# SCH_KPHONE.net
KiCad netlist of a schematic drawn in Altium Designer
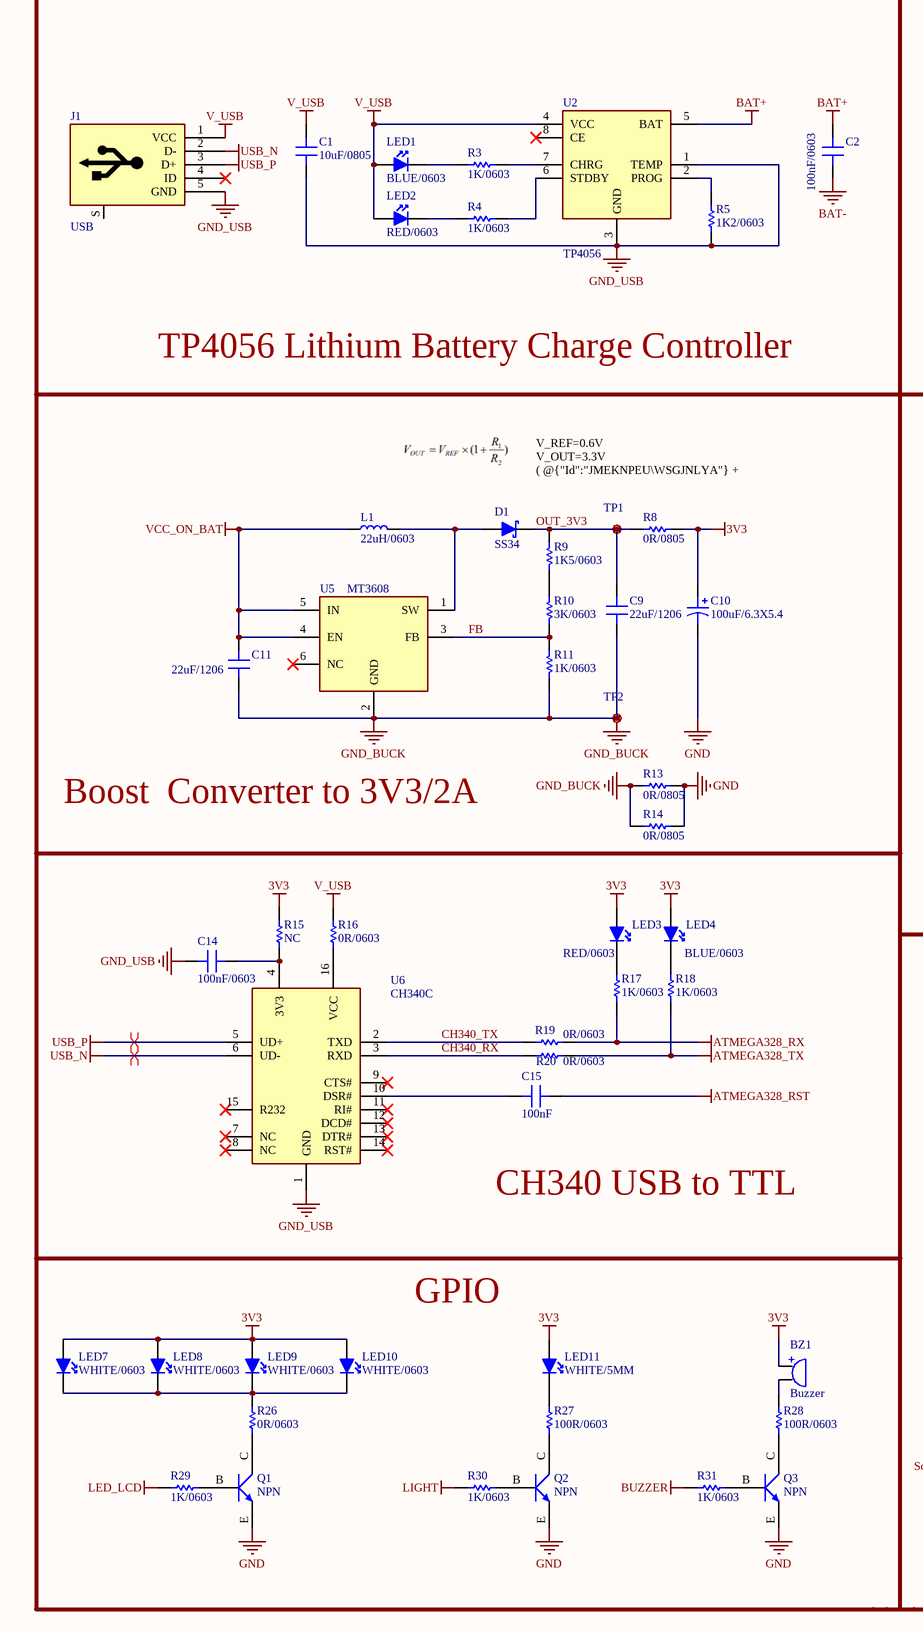
[diagram p0: SCH_KPHONE.SchDoc, left]
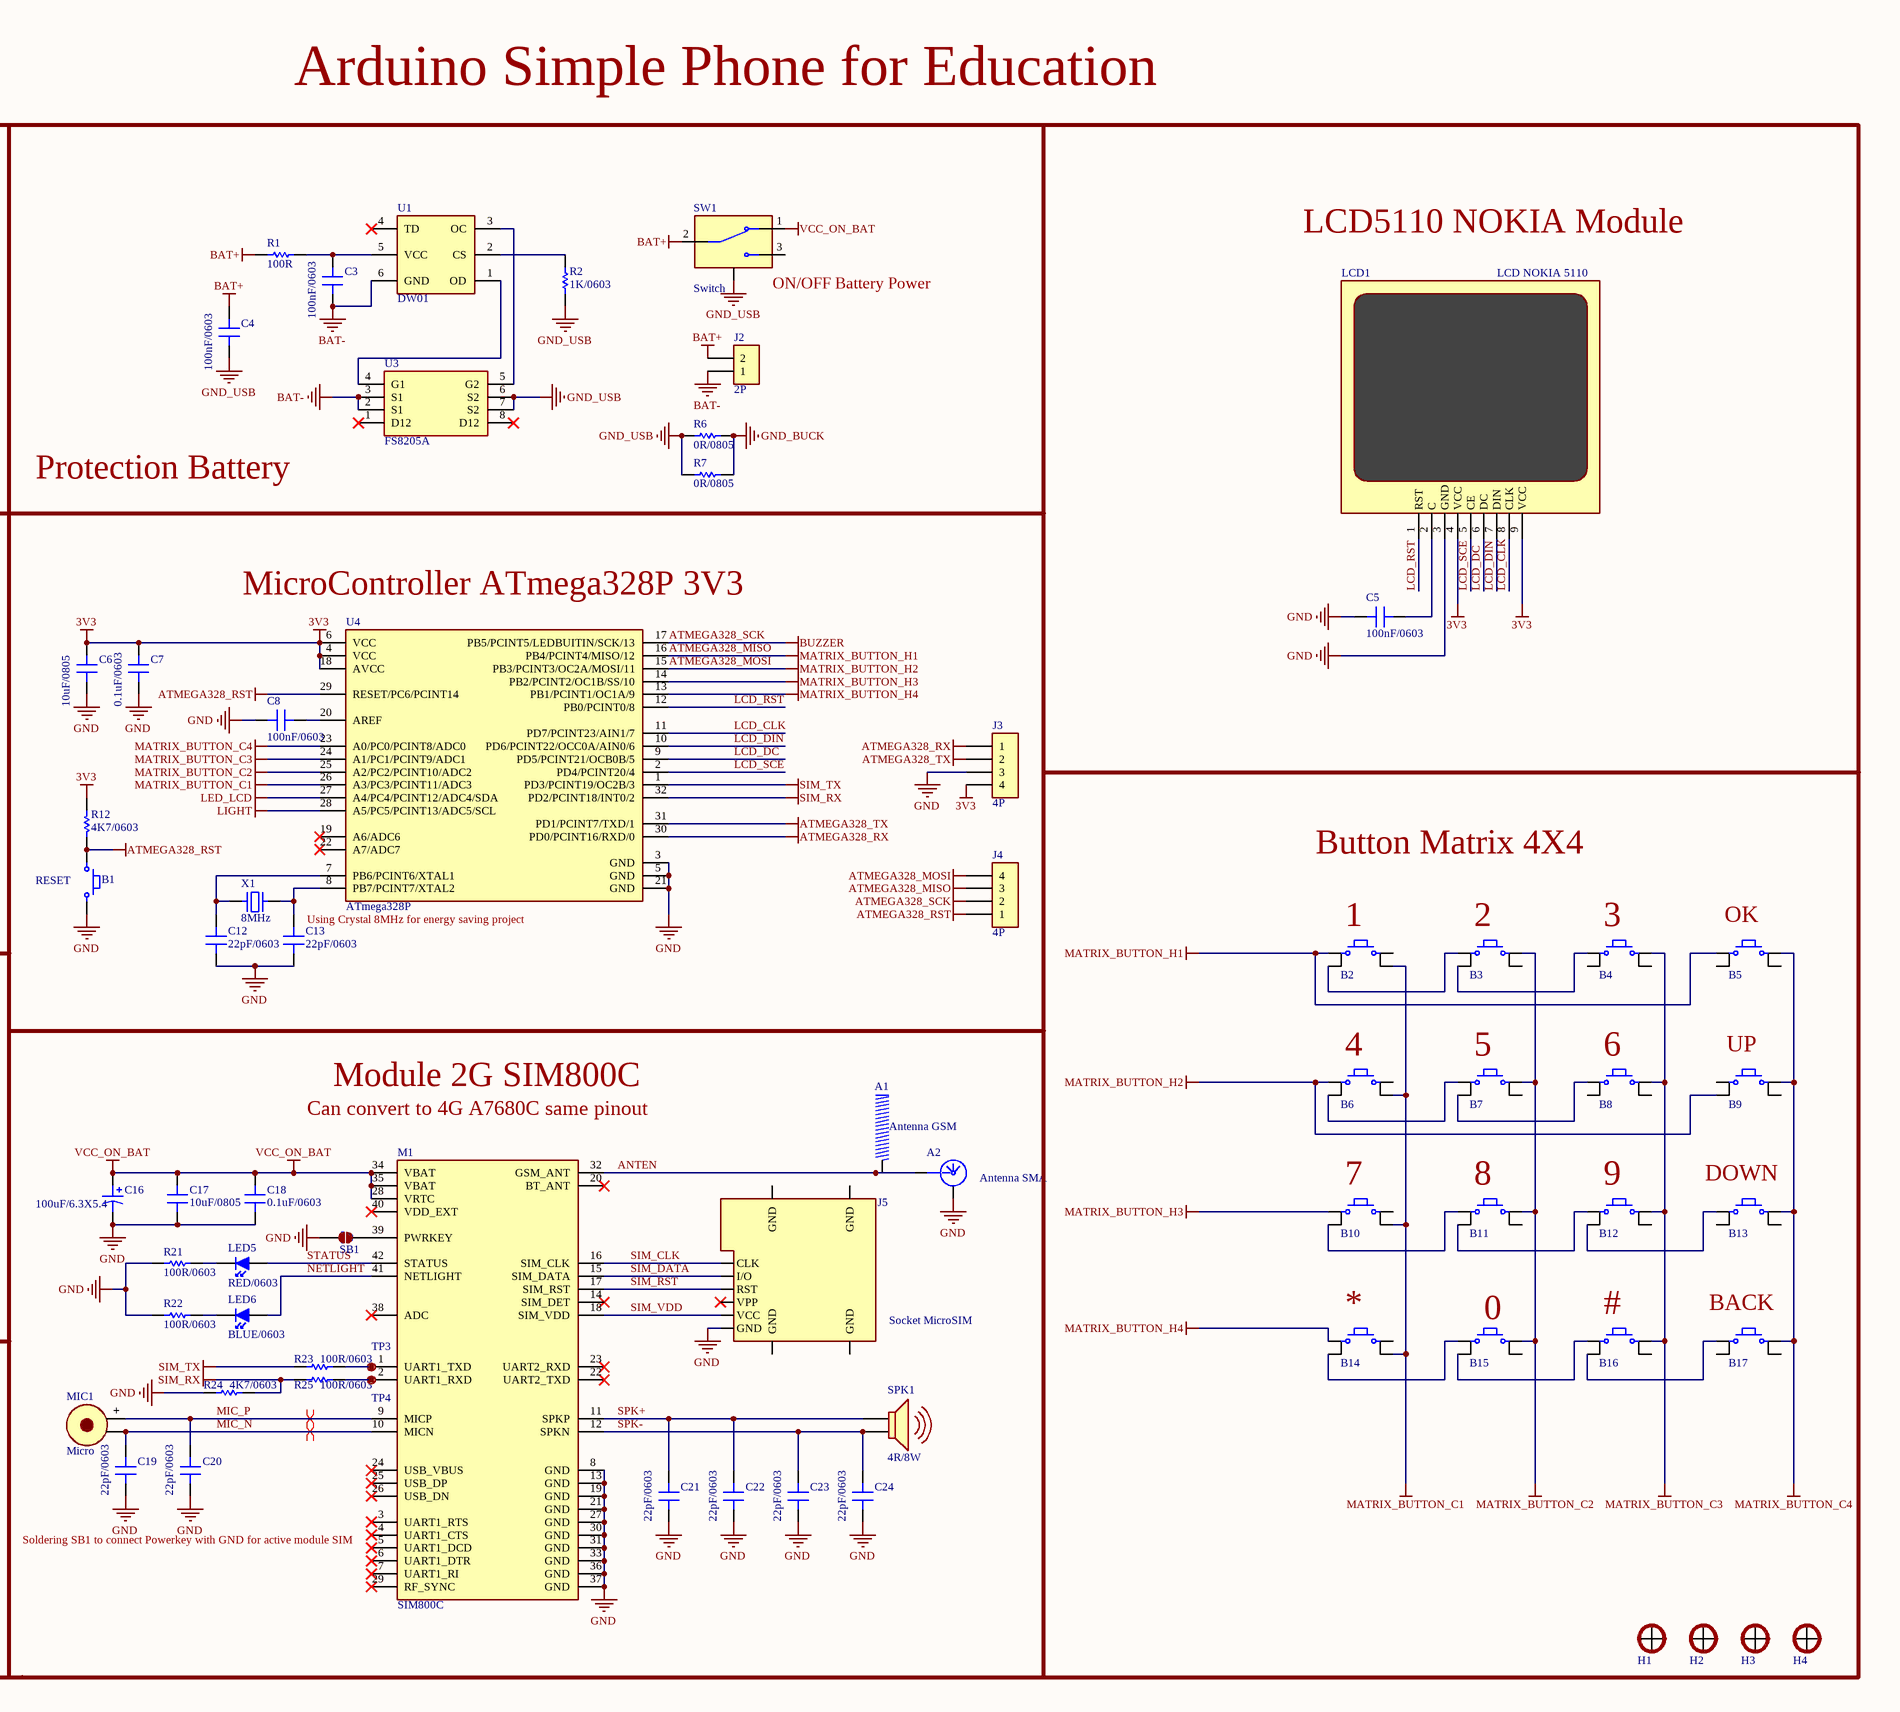
[diagram p1: SCH_KPHONE.SchDoc, right]

(export (version "E")
  (design (tool "Eeschema 10.0.6"))
  (components
    (comp (ref "A1")
      (value "Antenna GSM")
      (footprint "ANTEN GSM")
      (libsource (lib "LibraryKMA") (part "ANTEN GSM"))
    )
    (comp (ref "A2")
      (value "Antenna SMA")
      (footprint "ANTEN SMA FEMALE")
      (libsource (lib "LibraryKMA") (part "ANTENNA"))
    )
    (comp (ref "B1")
      (value "RESET")
      (footprint "BUTTON-SMD-2P-3x6x2.5MM")
      (description "Nút nhấn 2 chân")
      (libsource (lib "LibraryKMA") (part "BUTTON-2PIN"))
    )
    (comp (ref "B2")
      (value "Button")
      (footprint "BUTTON-SMD-4P-6X6X5MM")
      (description "Nút nhấn 4 chân")
      (libsource (lib "LibraryKMA") (part "BUTTON-4PIN"))
    )
    (comp (ref "B3")
      (value "Button")
      (footprint "BUTTON-SMD-4P-6X6X5MM")
      (description "Nút nhấn 4 chân")
      (libsource (lib "LibraryKMA") (part "BUTTON-4PIN"))
    )
    (comp (ref "B4")
      (value "Button")
      (footprint "BUTTON-SMD-4P-6X6X5MM")
      (description "Nút nhấn 4 chân")
      (libsource (lib "LibraryKMA") (part "BUTTON-4PIN"))
    )
    (comp (ref "B5")
      (value "Button")
      (footprint "BUTTON-SMD-4P-6X6X5MM")
      (description "Nút nhấn 4 chân")
      (libsource (lib "LibraryKMA") (part "BUTTON-4PIN"))
    )
    (comp (ref "B6")
      (value "Button")
      (footprint "BUTTON-SMD-4P-6X6X5MM")
      (description "Nút nhấn 4 chân")
      (libsource (lib "LibraryKMA") (part "BUTTON-4PIN"))
    )
    (comp (ref "B7")
      (value "Button")
      (footprint "BUTTON-SMD-4P-6X6X5MM")
      (description "Nút nhấn 4 chân")
      (libsource (lib "LibraryKMA") (part "BUTTON-4PIN"))
    )
    (comp (ref "B8")
      (value "Button")
      (footprint "BUTTON-SMD-4P-6X6X5MM")
      (description "Nút nhấn 4 chân")
      (libsource (lib "LibraryKMA") (part "BUTTON-4PIN"))
    )
    (comp (ref "B9")
      (value "Button")
      (footprint "BUTTON-SMD-4P-6X6X5MM")
      (description "Nút nhấn 4 chân")
      (libsource (lib "LibraryKMA") (part "BUTTON-4PIN"))
    )
    (comp (ref "B10")
      (value "Button")
      (footprint "BUTTON-SMD-4P-6X6X5MM")
      (description "Nút nhấn 4 chân")
      (libsource (lib "LibraryKMA") (part "BUTTON-4PIN"))
    )
    (comp (ref "B11")
      (value "Button")
      (footprint "BUTTON-SMD-4P-6X6X5MM")
      (description "Nút nhấn 4 chân")
      (libsource (lib "LibraryKMA") (part "BUTTON-4PIN"))
    )
    (comp (ref "B12")
      (value "Button")
      (footprint "BUTTON-SMD-4P-6X6X5MM")
      (description "Nút nhấn 4 chân")
      (libsource (lib "LibraryKMA") (part "BUTTON-4PIN"))
    )
    (comp (ref "B13")
      (value "Button")
      (footprint "BUTTON-SMD-4P-6X6X5MM")
      (description "Nút nhấn 4 chân")
      (libsource (lib "LibraryKMA") (part "BUTTON-4PIN"))
    )
    (comp (ref "B14")
      (value "Button")
      (footprint "BUTTON-SMD-4P-6X6X5MM")
      (description "Nút nhấn 4 chân")
      (libsource (lib "LibraryKMA") (part "BUTTON-4PIN"))
    )
    (comp (ref "B15")
      (value "Button")
      (footprint "BUTTON-SMD-4P-6X6X5MM")
      (description "Nút nhấn 4 chân")
      (libsource (lib "LibraryKMA") (part "BUTTON-4PIN"))
    )
    (comp (ref "B16")
      (value "Button")
      (footprint "BUTTON-SMD-4P-6X6X5MM")
      (description "Nút nhấn 4 chân")
      (libsource (lib "LibraryKMA") (part "BUTTON-4PIN"))
    )
    (comp (ref "B17")
      (value "Button")
      (footprint "BUTTON-SMD-4P-6X6X5MM")
      (description "Nút nhấn 4 chân")
      (libsource (lib "LibraryKMA") (part "BUTTON-4PIN"))
    )
    (comp (ref "BZ1")
      (value "Buzzer")
      (footprint "BUZZER_9055")
      (description "Còi chip")
      (libsource (lib "LibraryKMA") (part "BUZZER"))
    )
    (comp (ref "C1")
      (value "10uF/0805")
      (footprint "CAP-0805")
      (description "Tụ dán")
      (libsource (lib "LibraryKMA") (part "CAP-SMD"))
    )
    (comp (ref "C2")
      (value "100nF/0603")
      (footprint "CAP-0603")
      (description "Tụ dán")
      (libsource (lib "LibraryKMA") (part "CAP-SMD"))
    )
    (comp (ref "C3")
      (value "100nF/0603")
      (footprint "CAP-0603")
      (description "Tụ dán")
      (libsource (lib "LibraryKMA") (part "CAP-SMD"))
    )
    (comp (ref "C4")
      (value "100nF/0603")
      (footprint "CAP-0603")
      (description "Tụ dán")
      (libsource (lib "LibraryKMA") (part "CAP-SMD"))
    )
    (comp (ref "C5")
      (value "100nF/0603")
      (footprint "CAP-0603")
      (description "Tụ dán")
      (libsource (lib "LibraryKMA") (part "CAP-SMD"))
    )
    (comp (ref "C6")
      (value "10uF/0805")
      (footprint "CAP-0805")
      (description "Tụ dán")
      (libsource (lib "LibraryKMA") (part "CAP-SMD"))
    )
    (comp (ref "C7")
      (value "0.1uF/0603")
      (footprint "CAP-0603")
      (description "Tụ dán")
      (libsource (lib "LibraryKMA") (part "CAP-SMD"))
    )
    (comp (ref "C8")
      (value "100nF/0603")
      (footprint "CAP-0603")
      (description "Tụ dán")
      (libsource (lib "LibraryKMA") (part "CAP-SMD"))
    )
    (comp (ref "C9")
      (value "22uF/1206")
      (footprint "CAP-1206")
      (description "Tụ dán")
      (libsource (lib "LibraryKMA") (part "CAP-SMD"))
    )
    (comp (ref "C10")
      (value "100uF/6.3X5.4")
      (footprint "CAPP-SMD-ALU-6.3X5.4MM-D")
      (description "Tụ hoá dán")
      (libsource (lib "LibraryKMA") (part "CAPP-SMD"))
    )
    (comp (ref "C11")
      (value "22uF/1206")
      (footprint "CAP-1206")
      (description "Tụ dán")
      (libsource (lib "LibraryKMA") (part "CAP-SMD"))
    )
    (comp (ref "C12")
      (value "22pF/0603")
      (footprint "CAP-0603")
      (description "Tụ dán")
      (libsource (lib "LibraryKMA") (part "CAP-SMD"))
    )
    (comp (ref "C13")
      (value "22pF/0603")
      (footprint "CAP-0603")
      (description "Tụ dán")
      (libsource (lib "LibraryKMA") (part "CAP-SMD"))
    )
    (comp (ref "C14")
      (value "100nF/0603")
      (footprint "CAP-0603")
      (description "Tụ dán")
      (libsource (lib "LibraryKMA") (part "CAP-SMD"))
    )
    (comp (ref "C15")
      (value "100nF")
      (footprint "CAP-0603")
      (description "Tụ dán")
      (libsource (lib "LibraryKMA") (part "CAP-SMD"))
    )
    (comp (ref "C16")
      (value "100uF/6.3X5.4")
      (footprint "CAPP-SMD-ALU-6.3X5.4MM-D")
      (description "Tụ hoá dán")
      (libsource (lib "LibraryKMA") (part "CAPP-SMD"))
    )
    (comp (ref "C17")
      (value "10uF/0805")
      (footprint "CAP-0805")
      (description "Tụ dán")
      (libsource (lib "LibraryKMA") (part "CAP-SMD"))
    )
    (comp (ref "C18")
      (value "0.1uF/0603")
      (footprint "CAP-0603")
      (description "Tụ dán")
      (libsource (lib "LibraryKMA") (part "CAP-SMD"))
    )
    (comp (ref "C19")
      (value "22pF/0603")
      (footprint "CAP-0603")
      (description "Tụ dán")
      (libsource (lib "LibraryKMA") (part "CAP-SMD"))
    )
    (comp (ref "C20")
      (value "22pF/0603")
      (footprint "CAP-0603")
      (description "Tụ dán")
      (libsource (lib "LibraryKMA") (part "CAP-SMD"))
    )
    (comp (ref "C21")
      (value "22pF/0603")
      (footprint "CAP-0603")
      (description "Tụ dán")
      (libsource (lib "LibraryKMA") (part "CAP-SMD"))
    )
    (comp (ref "C22")
      (value "22pF/0603")
      (footprint "CAP-0603")
      (description "Tụ dán")
      (libsource (lib "LibraryKMA") (part "CAP-SMD"))
    )
    (comp (ref "C23")
      (value "22pF/0603")
      (footprint "CAP-0603")
      (description "Tụ dán")
      (libsource (lib "LibraryKMA") (part "CAP-SMD"))
    )
    (comp (ref "C24")
      (value "22pF/0603")
      (footprint "CAP-0603")
      (description "Tụ dán")
      (libsource (lib "LibraryKMA") (part "CAP-SMD"))
    )
    (comp (ref "D1")
      (value "SS34")
      (footprint "DIODE-SMD-DO-214AC")
      (description "Diode Schottky")
      (libsource (lib "LibraryKMA") (part "DIODE-SCHOTTKY"))
    )
    (comp (ref "H1")
      (value "~")
      (footprint "HOLE-M3")
      (description "Lỗ bắt vít")
      (libsource (lib "LibraryKMA") (part "HOLE-1P"))
    )
    (comp (ref "H2")
      (value "~")
      (footprint "HOLE-M3")
      (description "Lỗ bắt vít")
      (libsource (lib "LibraryKMA") (part "HOLE-1P"))
    )
    (comp (ref "H3")
      (value "~")
      (footprint "HOLE-M3")
      (description "Lỗ bắt vít")
      (libsource (lib "LibraryKMA") (part "HOLE-1P"))
    )
    (comp (ref "H4")
      (value "~")
      (footprint "HOLE-M3")
      (description "Lỗ bắt vít")
      (libsource (lib "LibraryKMA") (part "HOLE-1P"))
    )
    (comp (ref "J1")
      (value "USB")
      (footprint "USB-FEMALE-MICRO-DIP")
      (description "Cổng USB 5P")
      (fields (field (name "PART NUMBER") "USB-B-Mini"))
      (libsource (lib "LibraryKMA") (part "USB-5P"))
    )
    (comp (ref "J2")
      (value "2P")
      (footprint "XH2.54-2P-R")
      (description "Header 2P")
      (libsource (lib "LibraryKMA") (part "HEADER-2PIN"))
    )
    (comp (ref "J3")
      (value "4P")
      (footprint "JUMP-2.54-MALE-4P-NB")
      (description "Jump 4P")
      (libsource (lib "") (part "JUMP-4PIN_1"))
    )
    (comp (ref "J4")
      (value "4P")
      (footprint "JUMP-2.54-MALE-4P-NB")
      (description "Jump 4P")
      (libsource (lib "LibraryKMA") (part "JUMP-4PIN"))
    )
    (comp (ref "J5")
      (value "Socket MicroSIM")
      (footprint "SOCKET-MICRO-SIM-6P")
      (description "Khe cắm Sim")
      (libsource (lib "LibraryKMA") (part "SOCKET-SIM"))
    )
    (comp (ref "L1")
      (value "22uH/0603")
      (footprint "INDUCTOR-SMD-0630")
      (description "Cuộn cảm dán")
      (libsource (lib "LibraryKMA") (part "INDUCTOR-SMD"))
    )
    (comp (ref "LCD1")
      (value "LCD NOKIA 5110")
      (footprint "LCD NOKIA 5110-SMD")
      (description "LCD Module màn hình Nokia 5110 SMD PCB")
      (libsource (lib "LibraryKMA") (part "LCD NOKIA 5110 PCB"))
    )
    (comp (ref "LED1")
      (value "BLUE/0603")
      (footprint "LED-0603-BLUE")
      (description "Led dán")
      (libsource (lib "LibraryKMA") (part "LED-SMD"))
    )
    (comp (ref "LED2")
      (value "RED/0603")
      (footprint "LED-0603-RED")
      (description "Led dán")
      (libsource (lib "LibraryKMA") (part "LED-SMD"))
    )
    (comp (ref "LED3")
      (value "RED/0603")
      (footprint "LED-0603-RED")
      (description "Led dán")
      (libsource (lib "LibraryKMA") (part "LED-SMD"))
    )
    (comp (ref "LED4")
      (value "BLUE/0603")
      (footprint "LED-0603-BLUE")
      (description "Led dán")
      (libsource (lib "LibraryKMA") (part "LED-SMD"))
    )
    (comp (ref "LED5")
      (value "RED/0603")
      (footprint "LED-0603-RED")
      (description "Led dán")
      (libsource (lib "LibraryKMA") (part "LED-SMD"))
    )
    (comp (ref "LED6")
      (value "BLUE/0603")
      (footprint "LED-0603-BLUE")
      (description "Led dán")
      (libsource (lib "LibraryKMA") (part "LED-SMD"))
    )
    (comp (ref "LED7")
      (value "WHITE/0603")
      (footprint "LED-0603-WHITE")
      (description "Led dán")
      (libsource (lib "LibraryKMA") (part "LED-SMD"))
    )
    (comp (ref "LED8")
      (value "WHITE/0603")
      (footprint "LED-0603-WHITE")
      (description "Led dán")
      (libsource (lib "LibraryKMA") (part "LED-SMD"))
    )
    (comp (ref "LED9")
      (value "WHITE/0603")
      (footprint "LED-0603-WHITE")
      (description "Led dán")
      (libsource (lib "LibraryKMA") (part "LED-SMD"))
    )
    (comp (ref "LED10")
      (value "WHITE/0603")
      (footprint "LED-0603-WHITE")
      (description "Led dán")
      (libsource (lib "LibraryKMA") (part "LED-SMD"))
    )
    (comp (ref "LED11")
      (value "WHITE/5MM")
      (footprint "LED-5MM-RED-R")
      (description "Led cắm")
      (libsource (lib "LibraryKMA") (part "LED-DIP"))
    )
    (comp (ref "M1")
      (value "SIM800C")
      (footprint "SIM800C")
      (description "Module SIM800C hàn mạch PCB")
      (libsource (lib "LibraryKMA") (part "SIM800C"))
    )
    (comp (ref "MIC1")
      (value "Micro")
      (footprint "MICRO-DIP-4.5X2.2-P2.0")
      (description "Cảm biến âm thanh Microphone MIC")
      (libsource (lib "LibraryKMA") (part "MICRO-DIP"))
    )
    (comp (ref "Q1")
      (value "NPN")
      (footprint "TRANSISTOR-SOT-23-BCE")
      (description "Transistor NPN")
      (libsource (lib "LibraryKMA") (part "TRANSISTOR-NPN"))
    )
    (comp (ref "Q2")
      (value "NPN")
      (footprint "TRANSISTOR-SOT-23-BCE")
      (description "Transistor NPN")
      (libsource (lib "LibraryKMA") (part "TRANSISTOR-NPN"))
    )
    (comp (ref "Q3")
      (value "NPN")
      (footprint "TRANSISTOR-SOT-23-BCE")
      (description "Transistor NPN")
      (libsource (lib "LibraryKMA") (part "TRANSISTOR-NPN"))
    )
    (comp (ref "R1")
      (value "100R")
      (footprint "RES-0603")
      (description "Điện trở dán")
      (libsource (lib "LibraryKMA") (part "RES-SMD"))
    )
    (comp (ref "R2")
      (value "1K/0603")
      (footprint "RES-0603")
      (description "Điện trở dán")
      (libsource (lib "LibraryKMA") (part "RES-SMD"))
    )
    (comp (ref "R3")
      (value "1K/0603")
      (footprint "RES-0603")
      (description "Điện trở dán")
      (libsource (lib "LibraryKMA") (part "RES-SMD"))
    )
    (comp (ref "R4")
      (value "1K/0603")
      (footprint "RES-0603")
      (description "Điện trở dán")
      (libsource (lib "LibraryKMA") (part "RES-SMD"))
    )
    (comp (ref "R5")
      (value "1K2/0603")
      (footprint "RES-0603")
      (description "Điện trở dán")
      (libsource (lib "LibraryKMA") (part "RES-SMD"))
    )
    (comp (ref "R6")
      (value "0R/0805")
      (footprint "RES-0805")
      (description "Điện trở dán")
      (libsource (lib "LibraryKMA") (part "RES-SMD"))
    )
    (comp (ref "R7")
      (value "0R/0805")
      (footprint "RES-0805")
      (description "Điện trở dán")
      (libsource (lib "LibraryKMA") (part "RES-SMD"))
    )
    (comp (ref "R8")
      (value "0R/0805")
      (footprint "RES-0805")
      (description "Điện trở dán")
      (libsource (lib "LibraryKMA") (part "RES-SMD"))
    )
    (comp (ref "R9")
      (value "1K5/0603")
      (footprint "RES-0603")
      (description "Điện trở dán")
      (libsource (lib "LibraryKMA") (part "RES-SMD"))
    )
    (comp (ref "R10")
      (value "3K/0603")
      (footprint "RES-0603")
      (description "Điện trở dán")
      (libsource (lib "LibraryKMA") (part "RES-SMD"))
    )
    (comp (ref "R11")
      (value "1K/0603")
      (footprint "RES-0603")
      (description "Điện trở dán")
      (libsource (lib "LibraryKMA") (part "RES-SMD"))
    )
    (comp (ref "R12")
      (value "4K7/0603")
      (footprint "RES-0603")
      (description "Điện trở dán")
      (libsource (lib "LibraryKMA") (part "RES-SMD"))
    )
    (comp (ref "R13")
      (value "0R/0805")
      (footprint "RES-0805")
      (description "Điện trở dán")
      (libsource (lib "LibraryKMA") (part "RES-SMD"))
    )
    (comp (ref "R14")
      (value "0R/0805")
      (footprint "RES-0805")
      (description "Điện trở dán")
      (libsource (lib "LibraryKMA") (part "RES-SMD"))
    )
    (comp (ref "R15")
      (value "NC")
      (footprint "RES-0603")
      (description "Điện trở dán")
      (libsource (lib "LibraryKMA") (part "RES-SMD"))
    )
    (comp (ref "R16")
      (value "0R/0603")
      (footprint "RES-0603")
      (description "Điện trở dán")
      (libsource (lib "LibraryKMA") (part "RES-SMD"))
    )
    (comp (ref "R17")
      (value "1K/0603")
      (footprint "RES-0603")
      (description "Điện trở dán")
      (libsource (lib "LibraryKMA") (part "RES-SMD"))
    )
    (comp (ref "R18")
      (value "1K/0603")
      (footprint "RES-0603")
      (description "Điện trở dán")
      (libsource (lib "LibraryKMA") (part "RES-SMD"))
    )
    (comp (ref "R19")
      (value "0R/0603")
      (footprint "RES-0603")
      (description "Điện trở dán")
      (libsource (lib "LibraryKMA") (part "RES-SMD"))
    )
    (comp (ref "R20")
      (value "0R/0603")
      (footprint "RES-0603")
      (description "Điện trở dán")
      (libsource (lib "LibraryKMA") (part "RES-SMD"))
    )
    (comp (ref "R21")
      (value "100R/0603")
      (footprint "RES-0603")
      (description "Điện trở dán")
      (libsource (lib "LibraryKMA") (part "RES-SMD"))
    )
    (comp (ref "R22")
      (value "100R/0603")
      (footprint "RES-0603")
      (description "Điện trở dán")
      (libsource (lib "LibraryKMA") (part "RES-SMD"))
    )
    (comp (ref "R23")
      (value "100R/0603")
      (footprint "RES-0603")
      (description "Điện trở dán")
      (libsource (lib "LibraryKMA") (part "RES-SMD"))
    )
    (comp (ref "R24")
      (value "4K7/0603")
      (footprint "RES-0603")
      (description "Điện trở dán")
      (libsource (lib "LibraryKMA") (part "RES-SMD"))
    )
    (comp (ref "R25")
      (value "100R/0603")
      (footprint "RES-0603")
      (description "Điện trở dán")
      (libsource (lib "LibraryKMA") (part "RES-SMD"))
    )
    (comp (ref "R26")
      (value "0R/0603")
      (footprint "RES-0603")
      (description "Điện trở dán")
      (libsource (lib "LibraryKMA") (part "RES-SMD"))
    )
    (comp (ref "R27")
      (value "100R/0603")
      (footprint "RES-0603")
      (description "Điện trở dán")
      (libsource (lib "LibraryKMA") (part "RES-SMD"))
    )
    (comp (ref "R28")
      (value "100R/0603")
      (footprint "RES-0603")
      (description "Điện trở dán")
      (libsource (lib "LibraryKMA") (part "RES-SMD"))
    )
    (comp (ref "R29")
      (value "1K/0603")
      (footprint "RES-0603")
      (description "Điện trở dán")
      (libsource (lib "LibraryKMA") (part "RES-SMD"))
    )
    (comp (ref "R30")
      (value "1K/0603")
      (footprint "RES-0603")
      (description "Điện trở dán")
      (libsource (lib "LibraryKMA") (part "RES-SMD"))
    )
    (comp (ref "R31")
      (value "1K/0603")
      (footprint "RES-0603")
      (description "Điện trở dán")
      (libsource (lib "LibraryKMA") (part "RES-SMD"))
    )
    (comp (ref "SB1")
      (value "~")
      (footprint "SOLDER-BRIDGE-2")
      (description "Cầu hàn 2")
      (libsource (lib "LibraryKMA") (part "SOLDER-BRIDGE-2"))
    )
    (comp (ref "SPK1")
      (value "4R/8W")
      (footprint "SPEAKER 9X22MM")
      (description "Loa")
      (libsource (lib "LibraryKMA") (part "SPEAKER"))
    )
    (comp (ref "SW1")
      (value "Switch")
      (footprint "SWITCH-3PIN-R")
      (description "Công tắc gạt")
      (libsource (lib "LibraryKMA") (part "SWITCH-3PIN"))
    )
    (comp (ref "TP1")
      (value "TESTPOINT")
      (footprint "TESTPOINT")
      (description "Điểm Testpoint")
      (libsource (lib "LibraryKMA") (part "TESTPOINT"))
    )
    (comp (ref "TP2")
      (value "TESTPOINT")
      (footprint "TESTPOINT")
      (description "Điểm Testpoint")
      (libsource (lib "LibraryKMA") (part "TESTPOINT"))
    )
    (comp (ref "TP3")
      (value "TESTPOINT")
      (footprint "TESTPOINT")
      (description "Điểm Testpoint")
      (libsource (lib "LibraryKMA") (part "TESTPOINT"))
    )
    (comp (ref "TP4")
      (value "TESTPOINT")
      (footprint "TESTPOINT")
      (description "Điểm Testpoint")
      (libsource (lib "LibraryKMA") (part "TESTPOINT"))
    )
    (comp (ref "U1")
      (value "DW01")
      (footprint "SOT-23-6")
      (description "IC DW01 Bảo vệ Pin SOT23-6")
      (libsource (lib "LibraryKMA") (part "DW01"))
    )
    (comp (ref "U2")
      (value "TP4056")
      (footprint "TP4056")
      (description "IC TP4056 Quản lý sạc pin 3.7V SOP-8")
      (libsource (lib "LibraryKMA") (part "TP4056"))
    )
    (comp (ref "U3")
      (value "FS8205A")
      (footprint "FS8205A")
      (description "IC FS8205A Dual N-Mosfet TSSOP-8")
      (libsource (lib "LibraryKMA") (part "FS8205A"))
    )
    (comp (ref "U4")
      (value "ATmega328P")
      (footprint "TQFP-32")
      (description "IC ATmega328P IC MCU 8BIT 32KB FLASH 32P")
      (fields (field (name "MP") "STM8S003F3P6") (field (name "MF") "STMicroelectronics"))
      (libsource (lib "LibraryKMA") (part "ATMEGA328P"))
    )
    (comp (ref "U5")
      (value "MT3608")
      (footprint "SOT-23-6")
      (description "IC MT3608 DC-DC Converters 1.2MHz SOT-23-6")
      (fields (field (name "MF") "Aerosemi Technology Co., Ltd"))
      (libsource (lib "LibraryKMA") (part "MT3608"))
    )
    (comp (ref "U6")
      (value "CH340C")
      (footprint "SOP-16")
      (description "IC CH340C Chuyển đổi USB to TTL 2Mbps USB2.0 SOP-16")
      (fields (field (name "MP") "STM8S003F3P6") (field (name "MF") "STMicroelectronics"))
      (libsource (lib "LibraryKMA") (part "CH340C"))
    )
    (comp (ref "X1")
      (value "8MHz")
      (footprint "CRYSTAL-SMD-5032-2P")
      (description "Thạch anh 2P")
      (libsource (lib "LibraryKMA") (part "CRYSTAL-2P"))
    )
  )
  (nets
    (net (code "1") (name "/ANTEN") (class "Default")
      (node (ref "A1") (pin "1") (pinfunction "RF_1") (pintype "passive"))
      (node (ref "A2") (pin "1") (pinfunction "1_1") (pintype "passive"))
      (node (ref "M1") (pin "32") (pinfunction "GSM_ANT_32") (pintype "passive"))
    )
    (net (code "2") (name "/CH340_RX") (class "Default")
      (node (ref "R20") (pin "1") (pinfunction "1_1") (pintype "passive"))
      (node (ref "U6") (pin "3") (pinfunction "RXD_3") (pintype "passive"))
    )
    (net (code "3") (name "/CH340_TX") (class "Default")
      (node (ref "R19") (pin "1") (pinfunction "1_1") (pintype "passive"))
      (node (ref "U6") (pin "2") (pinfunction "TXD_2") (pintype "passive"))
    )
    (net (code "4") (name "/FB") (class "Default")
      (node (ref "R10") (pin "2") (pinfunction "2_2") (pintype "passive"))
      (node (ref "R11") (pin "1") (pinfunction "1_1") (pintype "passive"))
      (node (ref "U5") (pin "3") (pinfunction "FB_3") (pintype "passive"))
    )
    (net (code "5") (name "/LCD_CLK") (class "Default")
      (node (ref "LCD1") (pin "8") (pinfunction "CLK_8") (pintype "passive"))
      (node (ref "U4") (pin "11") (pinfunction "PD7/PCINT23/AIN1/7_11") (pintype "passive"))
    )
    (net (code "6") (name "/LCD_DC") (class "Default")
      (node (ref "LCD1") (pin "6") (pinfunction "DC_6") (pintype "passive"))
      (node (ref "U4") (pin "9") (pinfunction "PD5/PCINT21/OCB0B/5_9") (pintype "passive"))
    )
    (net (code "7") (name "/LCD_DIN") (class "Default")
      (node (ref "LCD1") (pin "7") (pinfunction "DIN_7") (pintype "passive"))
      (node (ref "U4") (pin "10") (pinfunction "PD6/PCINT22/OCC0A/AIN0/6_10") (pintype "passive"))
    )
    (net (code "8") (name "/LCD_RST") (class "Default")
      (node (ref "LCD1") (pin "1") (pinfunction "RST_1") (pintype "passive"))
      (node (ref "U4") (pin "12") (pinfunction "PB0/PCINT0/8_12") (pintype "passive"))
    )
    (net (code "9") (name "/LCD_SCE") (class "Default")
      (node (ref "LCD1") (pin "5") (pinfunction "CE_5") (pintype "passive"))
      (node (ref "U4") (pin "2") (pinfunction "PD4/PCINT20/4_2") (pintype "passive"))
    )
    (net (code "10") (name "/MIC_N") (class "Default")
      (node (ref "C19") (pin "1") (pinfunction "1_1") (pintype "passive"))
      (node (ref "M1") (pin "10") (pinfunction "MICN_10") (pintype "passive"))
      (node (ref "MIC1") (pin "2") (pinfunction "MIC-_2") (pintype "passive"))
    )
    (net (code "11") (name "/MIC_P") (class "Default")
      (node (ref "C20") (pin "2") (pinfunction "2_2") (pintype "passive"))
      (node (ref "M1") (pin "9") (pinfunction "MICP_9") (pintype "passive"))
      (node (ref "MIC1") (pin "1") (pinfunction "+_1") (pintype "passive"))
    )
    (net (code "12") (name "/NETLIGHT") (class "Default")
      (node (ref "LED6") (pin "1") (pinfunction "A_1") (pintype "passive"))
      (node (ref "M1") (pin "41") (pinfunction "NETLIGHT_41") (pintype "passive"))
    )
    (net (code "13") (name "/OUT_3V3") (class "Default")
      (node (ref "C9") (pin "2") (pinfunction "2_2") (pintype "passive"))
      (node (ref "D1") (pin "C") (pinfunction "K_C") (pintype "passive"))
      (node (ref "R8") (pin "1") (pinfunction "1_1") (pintype "passive"))
      (node (ref "R9") (pin "1") (pinfunction "1_1") (pintype "passive"))
      (node (ref "TP1") (pin "1") (pinfunction "1_1") (pintype "passive"))
    )
    (net (code "14") (name "/SIM_CLK") (class "Default")
      (node (ref "J5") (pin "C3") (pinfunction "CLK_C3") (pintype "passive"))
      (node (ref "M1") (pin "16") (pinfunction "SIM_CLK_16") (pintype "passive"))
    )
    (net (code "15") (name "/SIM_DATA") (class "Default")
      (node (ref "J5") (pin "C7") (pinfunction "I/O_C7") (pintype "passive"))
      (node (ref "M1") (pin "15") (pinfunction "SIM_DATA_15") (pintype "passive"))
    )
    (net (code "16") (name "/SIM_RST") (class "Default")
      (node (ref "J5") (pin "C2") (pinfunction "RST_C2") (pintype "passive"))
      (node (ref "M1") (pin "17") (pinfunction "SIM_RST_17") (pintype "passive"))
    )
    (net (code "17") (name "/SIM_VDD") (class "Default")
      (node (ref "J5") (pin "C1") (pinfunction "VCC_C1") (pintype "passive"))
      (node (ref "M1") (pin "18") (pinfunction "SIM_VDD_18") (pintype "passive"))
    )
    (net (code "18") (name "/SPK+") (class "Default")
      (node (ref "C21") (pin "2") (pinfunction "2_2") (pintype "passive"))
      (node (ref "C22") (pin "1") (pinfunction "1_1") (pintype "passive"))
      (node (ref "M1") (pin "11") (pinfunction "SPKP_11") (pintype "passive"))
      (node (ref "SPK1") (pin "2") (pinfunction "SPK-_2") (pintype "passive"))
    )
    (net (code "19") (name "/SPK-") (class "Default")
      (node (ref "C23") (pin "1") (pinfunction "1_1") (pintype "passive"))
      (node (ref "C24") (pin "1") (pinfunction "1_1") (pintype "passive"))
      (node (ref "M1") (pin "12") (pinfunction "SPKN_12") (pintype "passive"))
      (node (ref "SPK1") (pin "1") (pinfunction "SPK+_1") (pintype "passive"))
    )
    (net (code "20") (name "/STATUS") (class "Default")
      (node (ref "LED5") (pin "1") (pinfunction "A_1") (pintype "passive"))
      (node (ref "M1") (pin "42") (pinfunction "STATUS_42") (pintype "passive"))
    )
    (net (code "21") (name "3V3") (class "Default")
      (node (ref "BZ1") (pin "1") (pinfunction "1_1") (pintype "passive"))
      (node (ref "C10") (pin "1") (pinfunction "+_1") (pintype "passive"))
      (node (ref "C6") (pin "2") (pinfunction "2_2") (pintype "passive"))
      (node (ref "C7") (pin "2") (pinfunction "2_2") (pintype "passive"))
      (node (ref "J3") (pin "4") (pinfunction "4_4") (pintype "passive"))
      (node (ref "LCD1") (pin "4") (pinfunction "VCC_4") (pintype "passive"))
      (node (ref "LCD1") (pin "9") (pinfunction "VCC_9") (pintype "passive"))
      (node (ref "LED10") (pin "1") (pinfunction "A_1") (pintype "passive"))
      (node (ref "LED11") (pin "1") (pinfunction "A_1") (pintype "passive"))
      (node (ref "LED3") (pin "1") (pinfunction "A_1") (pintype "passive"))
      (node (ref "LED4") (pin "1") (pinfunction "A_1") (pintype "passive"))
      (node (ref "LED7") (pin "1") (pinfunction "A_1") (pintype "passive"))
      (node (ref "LED8") (pin "1") (pinfunction "A_1") (pintype "passive"))
      (node (ref "LED9") (pin "1") (pinfunction "A_1") (pintype "passive"))
      (node (ref "R12") (pin "1") (pinfunction "1_1") (pintype "passive"))
      (node (ref "R15") (pin "2") (pinfunction "2_2") (pintype "passive"))
      (node (ref "R8") (pin "2") (pinfunction "2_2") (pintype "passive"))
      (node (ref "U4") (pin "18") (pinfunction "AVCC_18") (pintype "passive"))
      (node (ref "U4") (pin "4") (pinfunction "VCC_4") (pintype "passive"))
      (node (ref "U4") (pin "6") (pinfunction "VCC_6") (pintype "passive"))
    )
    (net (code "22") (name "ATMEGA328_MISO") (class "Default")
      (node (ref "B2") (pin "1") (pinfunction "1_1") (pintype "passive"))
      (node (ref "B5") (pin "1") (pinfunction "1_1") (pintype "passive"))
      (node (ref "J4") (pin "3") (pinfunction "3_3") (pintype "passive"))
      (node (ref "U4") (pin "16") (pinfunction "PB4/PCINT4/MISO/12_16") (pintype "passive"))
    )
    (net (code "23") (name "ATMEGA328_MOSI") (class "Default")
      (node (ref "B6") (pin "1") (pinfunction "1_1") (pintype "passive"))
      (node (ref "B9") (pin "3") (pinfunction "3_3") (pintype "passive"))
      (node (ref "J4") (pin "4") (pinfunction "4_4") (pintype "passive"))
      (node (ref "U4") (pin "15") (pinfunction "PB3/PCINT3/OC2A/MOSI/11_15") (pintype "passive"))
    )
    (net (code "24") (name "ATMEGA328_RST") (class "Default")
      (node (ref "B1") (pin "2") (pinfunction "2_2") (pintype "passive"))
      (node (ref "C15") (pin "2") (pinfunction "2_2") (pintype "passive"))
      (node (ref "J4") (pin "1") (pinfunction "1_1") (pintype "passive"))
      (node (ref "R12") (pin "2") (pinfunction "2_2") (pintype "passive"))
      (node (ref "U4") (pin "29") (pinfunction "RESET/PC6/PCINT14_29") (pintype "passive"))
    )
    (net (code "25") (name "ATMEGA328_RX") (class "Default")
      (node (ref "J3") (pin "1") (pinfunction "1_1") (pintype "passive"))
      (node (ref "R17") (pin "2") (pinfunction "2_2") (pintype "passive"))
      (node (ref "R19") (pin "2") (pinfunction "2_2") (pintype "passive"))
      (node (ref "U4") (pin "30") (pinfunction "PD0/PCINT16/RXD/0_30") (pintype "passive"))
    )
    (net (code "26") (name "ATMEGA328_SCK") (class "Default")
      (node (ref "J4") (pin "2") (pinfunction "2_2") (pintype "passive"))
      (node (ref "R31") (pin "1") (pinfunction "1_1") (pintype "passive"))
      (node (ref "U4") (pin "17") (pinfunction "PB5/PCINT5/LEDBUITIN/SCK/13_17") (pintype "passive"))
    )
    (net (code "27") (name "ATMEGA328_TX") (class "Default")
      (node (ref "J3") (pin "2") (pinfunction "2_2") (pintype "passive"))
      (node (ref "R18") (pin "2") (pinfunction "2_2") (pintype "passive"))
      (node (ref "R20") (pin "2") (pinfunction "2_2") (pintype "passive"))
      (node (ref "U4") (pin "31") (pinfunction "PD1/PCINT7/TXD/1_31") (pintype "passive"))
    )
    (net (code "28") (name "BAT+") (class "Default")
      (node (ref "C2") (pin "1") (pinfunction "1_1") (pintype "passive"))
      (node (ref "C4") (pin "1") (pinfunction "1_1") (pintype "passive"))
      (node (ref "J2") (pin "2") (pinfunction "2_2") (pintype "passive"))
      (node (ref "R1") (pin "1") (pinfunction "1_1") (pintype "passive"))
      (node (ref "SW1") (pin "2") (pinfunction "COM1_2") (pintype "passive"))
      (node (ref "U2") (pin "5") (pinfunction "BAT_5") (pintype "passive"))
    )
    (net (code "29") (name "BAT-") (class "Default")
      (node (ref "C2") (pin "2") (pinfunction "2_2") (pintype "passive"))
      (node (ref "C3") (pin "2") (pinfunction "2_2") (pintype "passive"))
      (node (ref "J2") (pin "1") (pinfunction "1_1") (pintype "passive"))
      (node (ref "U1") (pin "6") (pinfunction "GND_6") (pintype "passive"))
      (node (ref "U3") (pin "2") (pinfunction "S1_2") (pintype "passive"))
      (node (ref "U3") (pin "3") (pinfunction "S1_3") (pintype "passive"))
    )
    (net (code "30") (name "GND") (class "Default")
      (node (ref "A2") (pin "2") (pinfunction "GND_2") (pintype "passive"))
      (node (ref "B1") (pin "1") (pinfunction "1_1") (pintype "passive"))
      (node (ref "C10") (pin "2") (pinfunction "-_2") (pintype "passive"))
      (node (ref "C12") (pin "2") (pinfunction "2_2") (pintype "passive"))
      (node (ref "C13") (pin "2") (pinfunction "2_2") (pintype "passive"))
      (node (ref "C16") (pin "2") (pinfunction "-_2") (pintype "passive"))
      (node (ref "C17") (pin "1") (pinfunction "1_1") (pintype "passive"))
      (node (ref "C18") (pin "1") (pinfunction "1_1") (pintype "passive"))
      (node (ref "C19") (pin "2") (pinfunction "2_2") (pintype "passive"))
      (node (ref "C20") (pin "1") (pinfunction "1_1") (pintype "passive"))
      (node (ref "C21") (pin "1") (pinfunction "1_1") (pintype "passive"))
      (node (ref "C22") (pin "2") (pinfunction "2_2") (pintype "passive"))
      (node (ref "C23") (pin "2") (pinfunction "2_2") (pintype "passive"))
      (node (ref "C24") (pin "2") (pinfunction "2_2") (pintype "passive"))
      (node (ref "C5") (pin "2") (pinfunction "2_2") (pintype "passive"))
      (node (ref "C6") (pin "1") (pinfunction "1_1") (pintype "passive"))
      (node (ref "C7") (pin "1") (pinfunction "1_1") (pintype "passive"))
      (node (ref "C8") (pin "1") (pinfunction "1_1") (pintype "passive"))
      (node (ref "J3") (pin "3") (pinfunction "3_3") (pintype "passive"))
      (node (ref "J5") (pin "C5") (pinfunction "GND_C5") (pintype "passive"))
      (node (ref "LCD1") (pin "3") (pinfunction "GND_3") (pintype "passive"))
      (node (ref "M1") (pin "13") (pinfunction "GND_13") (pintype "passive"))
      (node (ref "M1") (pin "19") (pinfunction "GND_19") (pintype "passive"))
      (node (ref "M1") (pin "21") (pinfunction "GND_21") (pintype "passive"))
      (node (ref "M1") (pin "27") (pinfunction "GND_27") (pintype "passive"))
      (node (ref "M1") (pin "30") (pinfunction "GND_30") (pintype "passive"))
      (node (ref "M1") (pin "31") (pinfunction "GND_31") (pintype "passive"))
      (node (ref "M1") (pin "33") (pinfunction "GND_33") (pintype "passive"))
      (node (ref "M1") (pin "36") (pinfunction "GND_36") (pintype "passive"))
      (node (ref "M1") (pin "37") (pinfunction "GND_37") (pintype "passive"))
      (node (ref "M1") (pin "8") (pinfunction "GND_8") (pintype "passive"))
      (node (ref "Q1") (pin "E") (pinfunction "E_E") (pintype "passive"))
      (node (ref "Q2") (pin "E") (pinfunction "E_E") (pintype "passive"))
      (node (ref "Q3") (pin "E") (pinfunction "E_E") (pintype "passive"))
      (node (ref "R13") (pin "1") (pinfunction "1_1") (pintype "passive"))
      (node (ref "R14") (pin "1") (pinfunction "1_1") (pintype "passive"))
      (node (ref "R21") (pin "2") (pinfunction "2_2") (pintype "passive"))
      (node (ref "R22") (pin "2") (pinfunction "2_2") (pintype "passive"))
      (node (ref "R24") (pin "2") (pinfunction "2_2") (pintype "passive"))
      (node (ref "SB1") (pin "1") (pinfunction "1_1") (pintype "passive"))
      (node (ref "U4") (pin "21") (pinfunction "GND_21") (pintype "passive"))
      (node (ref "U4") (pin "3") (pinfunction "GND_3") (pintype "passive"))
      (node (ref "U4") (pin "5") (pinfunction "GND_5") (pintype "passive"))
    )
    (net (code "31") (name "GND_BUCK") (class "Default")
      (node (ref "C11") (pin "1") (pinfunction "1_1") (pintype "passive"))
      (node (ref "C9") (pin "1") (pinfunction "1_1") (pintype "passive"))
      (node (ref "R11") (pin "2") (pinfunction "2_2") (pintype "passive"))
      (node (ref "R13") (pin "2") (pinfunction "2_2") (pintype "passive"))
      (node (ref "R14") (pin "2") (pinfunction "2_2") (pintype "passive"))
      (node (ref "R6") (pin "2") (pinfunction "2_2") (pintype "passive"))
      (node (ref "R7") (pin "2") (pinfunction "2_2") (pintype "passive"))
      (node (ref "TP2") (pin "1") (pinfunction "1_1") (pintype "passive"))
      (node (ref "U5") (pin "2") (pinfunction "GND_2") (pintype "passive"))
    )
    (net (code "32") (name "GND_USB") (class "Default")
      (node (ref "C1") (pin "1") (pinfunction "1_1") (pintype "passive"))
      (node (ref "C14") (pin "1") (pinfunction "1_1") (pintype "passive"))
      (node (ref "C4") (pin "2") (pinfunction "2_2") (pintype "passive"))
      (node (ref "J1") (pin "5") (pinfunction "GND_5") (pintype "passive"))
      (node (ref "R2") (pin "2") (pinfunction "2_2") (pintype "passive"))
      (node (ref "R5") (pin "1") (pinfunction "1_1") (pintype "passive"))
      (node (ref "R6") (pin "1") (pinfunction "1_1") (pintype "passive"))
      (node (ref "R7") (pin "1") (pinfunction "1_1") (pintype "passive"))
      (node (ref "SW1") (pin "0") (pinfunction "NO1_0") (pintype "passive"))
      (node (ref "U2") (pin "1") (pinfunction "TEMP_1") (pintype "passive"))
      (node (ref "U2") (pin "3") (pinfunction "GND_3") (pintype "passive"))
      (node (ref "U3") (pin "6") (pinfunction "S2_6") (pintype "passive"))
      (node (ref "U3") (pin "7") (pinfunction "S2_7") (pintype "passive"))
      (node (ref "U6") (pin "1") (pinfunction "GND_1") (pintype "passive"))
    )
    (net (code "33") (name "LED_LCD") (class "Default")
      (node (ref "R29") (pin "1") (pinfunction "1_1") (pintype "passive"))
      (node (ref "U4") (pin "27") (pinfunction "A4/PC4/PCINT12/ADC4/SDA_27") (pintype "passive"))
    )
    (net (code "34") (name "LIGHT") (class "Default")
      (node (ref "R30") (pin "1") (pinfunction "1_1") (pintype "passive"))
      (node (ref "U4") (pin "28") (pinfunction "A5/PC5/PCINT13/ADC5/SCL_28") (pintype "passive"))
    )
    (net (code "35") (name "MATRIX_BUTTON_C1") (class "Default")
      (node (ref "B10") (pin "4") (pinfunction "4_4") (pintype "passive"))
      (node (ref "B14") (pin "4") (pinfunction "4_4") (pintype "passive"))
      (node (ref "B2") (pin "4") (pinfunction "4_4") (pintype "passive"))
      (node (ref "B6") (pin "4") (pinfunction "4_4") (pintype "passive"))
      (node (ref "U4") (pin "26") (pinfunction "A3/PC3/PCINT11/ADC3_26") (pintype "passive"))
    )
    (net (code "36") (name "MATRIX_BUTTON_C2") (class "Default")
      (node (ref "B11") (pin "2") (pinfunction "2_2") (pintype "passive"))
      (node (ref "B15") (pin "2") (pinfunction "2_2") (pintype "passive"))
      (node (ref "B3") (pin "2") (pinfunction "2_2") (pintype "passive"))
      (node (ref "B7") (pin "2") (pinfunction "2_2") (pintype "passive"))
      (node (ref "U4") (pin "25") (pinfunction "A2/PC2/PCINT10/ADC2_25") (pintype "passive"))
    )
    (net (code "37") (name "MATRIX_BUTTON_C3") (class "Default")
      (node (ref "B12") (pin "2") (pinfunction "2_2") (pintype "passive"))
      (node (ref "B16") (pin "2") (pinfunction "2_2") (pintype "passive"))
      (node (ref "B4") (pin "2") (pinfunction "2_2") (pintype "passive"))
      (node (ref "B8") (pin "2") (pinfunction "2_2") (pintype "passive"))
      (node (ref "U4") (pin "24") (pinfunction "A1/PC1/PCINT9/ADC1_24") (pintype "passive"))
    )
    (net (code "38") (name "MATRIX_BUTTON_C4") (class "Default")
      (node (ref "B13") (pin "2") (pinfunction "2_2") (pintype "passive"))
      (node (ref "B17") (pin "2") (pinfunction "2_2") (pintype "passive"))
      (node (ref "B5") (pin "2") (pinfunction "2_2") (pintype "passive"))
      (node (ref "B9") (pin "2") (pinfunction "2_2") (pintype "passive"))
      (node (ref "U4") (pin "23") (pinfunction "A0/PC0/PCINT8/ADC0_23") (pintype "passive"))
    )
    (net (code "39") (name "MATRIX_BUTTON_H3") (class "Default")
      (node (ref "B10") (pin "1") (pinfunction "1_1") (pintype "passive"))
      (node (ref "U4") (pin "14") (pinfunction "PB2/PCINT2/OC1B/SS/10_14") (pintype "passive"))
    )
    (net (code "40") (name "MATRIX_BUTTON_H4") (class "Default")
      (node (ref "B14") (pin "1") (pinfunction "1_1") (pintype "passive"))
      (node (ref "U4") (pin "13") (pinfunction "PB1/PCINT1/OC1A/9_13") (pintype "passive"))
    )
    (net (code "41") (name "Net-(B2-Pad3)") (class "Default")
      (node (ref "B2") (pin "3") (pinfunction "3_3") (pintype "passive"))
      (node (ref "B3") (pin "1") (pinfunction "1_1") (pintype "passive"))
    )
    (net (code "42") (name "Net-(B3-Pad3)") (class "Default")
      (node (ref "B3") (pin "3") (pinfunction "3_3") (pintype "passive"))
      (node (ref "B4") (pin "1") (pinfunction "1_1") (pintype "passive"))
    )
    (net (code "43") (name "Net-(B6-Pad3)") (class "Default")
      (node (ref "B6") (pin "3") (pinfunction "3_3") (pintype "passive"))
      (node (ref "B7") (pin "1") (pinfunction "1_1") (pintype "passive"))
    )
    (net (code "44") (name "Net-(B7-Pad3)") (class "Default")
      (node (ref "B7") (pin "3") (pinfunction "3_3") (pintype "passive"))
      (node (ref "B8") (pin "1") (pinfunction "1_1") (pintype "passive"))
    )
    (net (code "45") (name "Net-(B10-Pad3)") (class "Default")
      (node (ref "B10") (pin "3") (pinfunction "3_3") (pintype "passive"))
      (node (ref "B11") (pin "1") (pinfunction "1_1") (pintype "passive"))
    )
    (net (code "46") (name "Net-(B11-Pad3)") (class "Default")
      (node (ref "B11") (pin "3") (pinfunction "3_3") (pintype "passive"))
      (node (ref "B12") (pin "1") (pinfunction "1_1") (pintype "passive"))
    )
    (net (code "47") (name "Net-(B12-Pad3)") (class "Default")
      (node (ref "B12") (pin "3") (pinfunction "3_3") (pintype "passive"))
      (node (ref "B13") (pin "1") (pinfunction "1_1") (pintype "passive"))
    )
    (net (code "48") (name "Net-(B14-Pad3)") (class "Default")
      (node (ref "B14") (pin "3") (pinfunction "3_3") (pintype "passive"))
      (node (ref "B15") (pin "1") (pinfunction "1_1") (pintype "passive"))
    )
    (net (code "49") (name "Net-(B15-Pad3)") (class "Default")
      (node (ref "B15") (pin "3") (pinfunction "3_3") (pintype "passive"))
      (node (ref "B16") (pin "1") (pinfunction "1_1") (pintype "passive"))
    )
    (net (code "50") (name "Net-(B16-Pad3)") (class "Default")
      (node (ref "B16") (pin "3") (pinfunction "3_3") (pintype "passive"))
      (node (ref "B17") (pin "1") (pinfunction "1_1") (pintype "passive"))
    )
    (net (code "51") (name "Net-(BZ1-Pad2)") (class "Default")
      (node (ref "BZ1") (pin "2") (pinfunction "2_2") (pintype "passive"))
      (node (ref "R28") (pin "1") (pinfunction "1_1") (pintype "passive"))
    )
    (net (code "52") (name "Net-(LCD1-C)") (class "Default")
      (node (ref "C5") (pin "1") (pinfunction "1_1") (pintype "passive"))
      (node (ref "LCD1") (pin "2") (pinfunction "C_2") (pintype "passive"))
    )
    (net (code "53") (name "Net-(LED1-K)") (class "Default")
      (node (ref "LED1") (pin "2") (pinfunction "K_2") (pintype "passive"))
      (node (ref "R3") (pin "1") (pinfunction "1_1") (pintype "passive"))
    )
    (net (code "54") (name "Net-(LED2-K)") (class "Default")
      (node (ref "LED2") (pin "2") (pinfunction "K_2") (pintype "passive"))
      (node (ref "R4") (pin "1") (pinfunction "1_1") (pintype "passive"))
    )
    (net (code "55") (name "Net-(LED3-K)") (class "Default")
      (node (ref "LED3") (pin "2") (pinfunction "K_2") (pintype "passive"))
      (node (ref "R17") (pin "1") (pinfunction "1_1") (pintype "passive"))
    )
    (net (code "56") (name "Net-(LED4-K)") (class "Default")
      (node (ref "LED4") (pin "2") (pinfunction "K_2") (pintype "passive"))
      (node (ref "R18") (pin "1") (pinfunction "1_1") (pintype "passive"))
    )
    (net (code "57") (name "Net-(LED5-K)") (class "Default")
      (node (ref "LED5") (pin "2") (pinfunction "K_2") (pintype "passive"))
      (node (ref "R21") (pin "1") (pinfunction "1_1") (pintype "passive"))
    )
    (net (code "58") (name "Net-(LED6-K)") (class "Default")
      (node (ref "LED6") (pin "2") (pinfunction "K_2") (pintype "passive"))
      (node (ref "R22") (pin "1") (pinfunction "1_1") (pintype "passive"))
    )
    (net (code "59") (name "Net-(LED10-K)") (class "Default")
      (node (ref "LED10") (pin "2") (pinfunction "K_2") (pintype "passive"))
      (node (ref "LED7") (pin "2") (pinfunction "K_2") (pintype "passive"))
      (node (ref "LED8") (pin "2") (pinfunction "K_2") (pintype "passive"))
      (node (ref "LED9") (pin "2") (pinfunction "K_2") (pintype "passive"))
      (node (ref "R26") (pin "1") (pinfunction "1_1") (pintype "passive"))
    )
    (net (code "60") (name "Net-(LED11-K)") (class "Default")
      (node (ref "LED11") (pin "2") (pinfunction "K_2") (pintype "passive"))
      (node (ref "R27") (pin "1") (pinfunction "1_1") (pintype "passive"))
    )
    (net (code "61") (name "Net-(M1-PWRKEY)") (class "Default")
      (node (ref "M1") (pin "39") (pinfunction "PWRKEY_39") (pintype "passive"))
      (node (ref "SB1") (pin "2") (pinfunction "2_2") (pintype "passive"))
    )
    (net (code "62") (name "Net-(M1-UART1_RXD)") (class "Default")
      (node (ref "M1") (pin "2") (pinfunction "UART1_RXD_2") (pintype "passive"))
      (node (ref "R25") (pin "2") (pinfunction "2_2") (pintype "passive"))
      (node (ref "TP4") (pin "1") (pinfunction "1_1") (pintype "passive"))
    )
    (net (code "63") (name "Net-(M1-UART1_TXD)") (class "Default")
      (node (ref "M1") (pin "1") (pinfunction "UART1_TXD_1") (pintype "passive"))
      (node (ref "R23") (pin "1") (pinfunction "1_1") (pintype "passive"))
      (node (ref "TP3") (pin "1") (pinfunction "1_1") (pintype "passive"))
    )
    (net (code "64") (name "Net-(Q1-PadB)") (class "Default")
      (node (ref "Q1") (pin "B") (pinfunction "B_B") (pintype "passive"))
      (node (ref "R29") (pin "2") (pinfunction "2_2") (pintype "passive"))
    )
    (net (code "65") (name "Net-(Q1-PadC)") (class "Default")
      (node (ref "Q1") (pin "C") (pinfunction "C_C") (pintype "passive"))
      (node (ref "R26") (pin "2") (pinfunction "2_2") (pintype "passive"))
    )
    (net (code "66") (name "Net-(Q2-PadB)") (class "Default")
      (node (ref "Q2") (pin "B") (pinfunction "B_B") (pintype "passive"))
      (node (ref "R30") (pin "2") (pinfunction "2_2") (pintype "passive"))
    )
    (net (code "67") (name "Net-(Q2-PadC)") (class "Default")
      (node (ref "Q2") (pin "C") (pinfunction "C_C") (pintype "passive"))
      (node (ref "R27") (pin "2") (pinfunction "2_2") (pintype "passive"))
    )
    (net (code "68") (name "Net-(Q3-PadB)") (class "Default")
      (node (ref "Q3") (pin "B") (pinfunction "B_B") (pintype "passive"))
      (node (ref "R31") (pin "2") (pinfunction "2_2") (pintype "passive"))
    )
    (net (code "69") (name "Net-(Q3-PadC)") (class "Default")
      (node (ref "Q3") (pin "C") (pinfunction "C_C") (pintype "passive"))
      (node (ref "R28") (pin "2") (pinfunction "2_2") (pintype "passive"))
    )
    (net (code "70") (name "Net-(R10-Pad1)") (class "Default")
      (node (ref "R10") (pin "1") (pinfunction "1_1") (pintype "passive"))
      (node (ref "R9") (pin "2") (pinfunction "2_2") (pintype "passive"))
    )
    (net (code "71") (name "Net-(U1-CS)") (class "Default")
      (node (ref "R2") (pin "1") (pinfunction "1_1") (pintype "passive"))
      (node (ref "U1") (pin "2") (pinfunction "CS_2") (pintype "passive"))
    )
    (net (code "72") (name "Net-(U1-OC)") (class "Default")
      (node (ref "U1") (pin "3") (pinfunction "OC_3") (pintype "passive"))
      (node (ref "U3") (pin "5") (pinfunction "G2_5") (pintype "passive"))
    )
    (net (code "73") (name "Net-(U1-OD)") (class "Default")
      (node (ref "U1") (pin "1") (pinfunction "OD_1") (pintype "passive"))
      (node (ref "U3") (pin "4") (pinfunction "G1_4") (pintype "passive"))
    )
    (net (code "74") (name "Net-(U1-VCC)") (class "Default")
      (node (ref "C3") (pin "1") (pinfunction "1_1") (pintype "passive"))
      (node (ref "R1") (pin "2") (pinfunction "2_2") (pintype "passive"))
      (node (ref "U1") (pin "5") (pinfunction "VCC_5") (pintype "passive"))
    )
    (net (code "75") (name "Net-(U2-CHRG)") (class "Default")
      (node (ref "R3") (pin "2") (pinfunction "2_2") (pintype "passive"))
      (node (ref "U2") (pin "7") (pinfunction "CHRG_7") (pintype "passive"))
    )
    (net (code "76") (name "Net-(U2-PROG)") (class "Default")
      (node (ref "R5") (pin "2") (pinfunction "2_2") (pintype "passive"))
      (node (ref "U2") (pin "2") (pinfunction "PROG_2") (pintype "passive"))
    )
    (net (code "77") (name "Net-(U2-STDBY)") (class "Default")
      (node (ref "R4") (pin "2") (pinfunction "2_2") (pintype "passive"))
      (node (ref "U2") (pin "6") (pinfunction "STDBY_6") (pintype "passive"))
    )
    (net (code "78") (name "Net-(U4-AREF)") (class "Default")
      (node (ref "C8") (pin "2") (pinfunction "2_2") (pintype "passive"))
      (node (ref "U4") (pin "20") (pinfunction "AREF_20") (pintype "passive"))
    )
    (net (code "79") (name "Net-(U4-PB6{slash}PCINT6{slash}XTAL1)") (class "Default")
      (node (ref "C12") (pin "1") (pinfunction "1_1") (pintype "passive"))
      (node (ref "U4") (pin "7") (pinfunction "PB6/PCINT6/XTAL1_7") (pintype "passive"))
      (node (ref "X1") (pin "1") (pinfunction "1_1") (pintype "passive"))
    )
    (net (code "80") (name "Net-(U4-PB7{slash}PCINT7{slash}XTAL2)") (class "Default")
      (node (ref "C13") (pin "1") (pinfunction "1_1") (pintype "passive"))
      (node (ref "U4") (pin "8") (pinfunction "PB7/PCINT7/XTAL2_8") (pintype "passive"))
      (node (ref "X1") (pin "2") (pinfunction "2_2") (pintype "passive"))
    )
    (net (code "81") (name "Net-(U5-SW)") (class "Default")
      (node (ref "D1") (pin "A") (pinfunction "A_A") (pintype "passive"))
      (node (ref "L1") (pin "2") (pinfunction "2_2") (pintype "passive"))
      (node (ref "U5") (pin "1") (pinfunction "SW_1") (pintype "passive"))
    )
    (net (code "82") (name "Net-(U6-3V3)") (class "Default")
      (node (ref "C14") (pin "2") (pinfunction "2_2") (pintype "passive"))
      (node (ref "R15") (pin "1") (pinfunction "1_1") (pintype "passive"))
      (node (ref "U6") (pin "4") (pinfunction "3V3_4") (pintype "passive"))
    )
    (net (code "83") (name "Net-(U6-DSR#)") (class "Default")
      (node (ref "C15") (pin "1") (pinfunction "1_1") (pintype "passive"))
      (node (ref "U6") (pin "10") (pinfunction "DSR#_10") (pintype "passive"))
    )
    (net (code "84") (name "Net-(U6-VCC)") (class "Default")
      (node (ref "R16") (pin "1") (pinfunction "1_1") (pintype "passive"))
      (node (ref "U6") (pin "16") (pinfunction "VCC_16") (pintype "passive"))
    )
    (net (code "85") (name "SIM_RX") (class "Default")
      (node (ref "R24") (pin "1") (pinfunction "1_1") (pintype "passive"))
      (node (ref "R25") (pin "1") (pinfunction "1_1") (pintype "passive"))
      (node (ref "U4") (pin "32") (pinfunction "PD2/PCINT18/INT0/2_32") (pintype "passive"))
    )
    (net (code "86") (name "SIM_TX") (class "Default")
      (node (ref "R23") (pin "2") (pinfunction "2_2") (pintype "passive"))
      (node (ref "U4") (pin "1") (pinfunction "PD3/PCINT19/OC2B/3_1") (pintype "passive"))
    )
    (net (code "87") (name "USB_N") (class "Default")
      (node (ref "J1") (pin "2") (pinfunction "D-_2") (pintype "passive"))
      (node (ref "U6") (pin "6") (pinfunction "UD-_6") (pintype "passive"))
    )
    (net (code "88") (name "USB_P") (class "Default")
      (node (ref "J1") (pin "3") (pinfunction "D+_3") (pintype "passive"))
      (node (ref "U6") (pin "5") (pinfunction "UD+_5") (pintype "passive"))
    )
    (net (code "89") (name "VCC_ON_BAT") (class "Default")
      (node (ref "C11") (pin "2") (pinfunction "2_2") (pintype "passive"))
      (node (ref "C16") (pin "1") (pinfunction "+_1") (pintype "passive"))
      (node (ref "C17") (pin "2") (pinfunction "2_2") (pintype "passive"))
      (node (ref "C18") (pin "2") (pinfunction "2_2") (pintype "passive"))
      (node (ref "L1") (pin "1") (pinfunction "1_1") (pintype "passive"))
      (node (ref "M1") (pin "28") (pinfunction "VRTC_28") (pintype "passive"))
      (node (ref "M1") (pin "34") (pinfunction "VBAT_34") (pintype "passive"))
      (node (ref "M1") (pin "35") (pinfunction "VBAT_35") (pintype "passive"))
      (node (ref "SW1") (pin "1") (pinfunction "NC1_1") (pintype "passive"))
      (node (ref "U5") (pin "4") (pinfunction "EN_4") (pintype "passive"))
      (node (ref "U5") (pin "5") (pinfunction "IN_5") (pintype "passive"))
    )
    (net (code "90") (name "V_USB") (class "Default")
      (node (ref "C1") (pin "2") (pinfunction "2_2") (pintype "passive"))
      (node (ref "J1") (pin "1") (pinfunction "VCC_1") (pintype "passive"))
      (node (ref "LED1") (pin "1") (pinfunction "A_1") (pintype "passive"))
      (node (ref "LED2") (pin "1") (pinfunction "A_1") (pintype "passive"))
      (node (ref "R16") (pin "2") (pinfunction "2_2") (pintype "passive"))
      (node (ref "U2") (pin "4") (pinfunction "VCC_4") (pintype "passive"))
    )
    (net (code "91") (name "unconnected-(B2-Pad2)") (class "Default")
      (node (ref "B2") (pin "2") (pinfunction "2_2") (pintype "passive"))
    )
    (net (code "92") (name "unconnected-(B3-Pad4)") (class "Default")
      (node (ref "B3") (pin "4") (pinfunction "4_4") (pintype "passive"))
    )
    (net (code "93") (name "unconnected-(B4-Pad3)") (class "Default")
      (node (ref "B4") (pin "3") (pinfunction "3_3") (pintype "passive"))
    )
    (net (code "94") (name "unconnected-(B4-Pad4)") (class "Default")
      (node (ref "B4") (pin "4") (pinfunction "4_4") (pintype "passive"))
    )
    (net (code "95") (name "unconnected-(B5-Pad3)") (class "Default")
      (node (ref "B5") (pin "3") (pinfunction "3_3") (pintype "passive"))
    )
    (net (code "96") (name "unconnected-(B5-Pad4)") (class "Default")
      (node (ref "B5") (pin "4") (pinfunction "4_4") (pintype "passive"))
    )
    (net (code "97") (name "unconnected-(B6-Pad2)") (class "Default")
      (node (ref "B6") (pin "2") (pinfunction "2_2") (pintype "passive"))
    )
    (net (code "98") (name "unconnected-(B7-Pad4)") (class "Default")
      (node (ref "B7") (pin "4") (pinfunction "4_4") (pintype "passive"))
    )
    (net (code "99") (name "unconnected-(B8-Pad3)") (class "Default")
      (node (ref "B8") (pin "3") (pinfunction "3_3") (pintype "passive"))
    )
    (net (code "100") (name "unconnected-(B8-Pad4)") (class "Default")
      (node (ref "B8") (pin "4") (pinfunction "4_4") (pintype "passive"))
    )
    (net (code "101") (name "unconnected-(B9-Pad1)") (class "Default")
      (node (ref "B9") (pin "1") (pinfunction "1_1") (pintype "passive"))
    )
    (net (code "102") (name "unconnected-(B9-Pad4)") (class "Default")
      (node (ref "B9") (pin "4") (pinfunction "4_4") (pintype "passive"))
    )
    (net (code "103") (name "unconnected-(B10-Pad2)") (class "Default")
      (node (ref "B10") (pin "2") (pinfunction "2_2") (pintype "passive"))
    )
    (net (code "104") (name "unconnected-(B11-Pad4)") (class "Default")
      (node (ref "B11") (pin "4") (pinfunction "4_4") (pintype "passive"))
    )
    (net (code "105") (name "unconnected-(B12-Pad4)") (class "Default")
      (node (ref "B12") (pin "4") (pinfunction "4_4") (pintype "passive"))
    )
    (net (code "106") (name "unconnected-(B13-Pad3)") (class "Default")
      (node (ref "B13") (pin "3") (pinfunction "3_3") (pintype "passive"))
    )
    (net (code "107") (name "unconnected-(B13-Pad4)") (class "Default")
      (node (ref "B13") (pin "4") (pinfunction "4_4") (pintype "passive"))
    )
    (net (code "108") (name "unconnected-(B14-Pad2)") (class "Default")
      (node (ref "B14") (pin "2") (pinfunction "2_2") (pintype "passive"))
    )
    (net (code "109") (name "unconnected-(B15-Pad4)") (class "Default")
      (node (ref "B15") (pin "4") (pinfunction "4_4") (pintype "passive"))
    )
    (net (code "110") (name "unconnected-(B16-Pad4)") (class "Default")
      (node (ref "B16") (pin "4") (pinfunction "4_4") (pintype "passive"))
    )
    (net (code "111") (name "unconnected-(B17-Pad3)") (class "Default")
      (node (ref "B17") (pin "3") (pinfunction "3_3") (pintype "passive"))
    )
    (net (code "112") (name "unconnected-(B17-Pad4)") (class "Default")
      (node (ref "B17") (pin "4") (pinfunction "4_4") (pintype "passive"))
    )
    (net (code "113") (name "unconnected-(H1-Pad1)") (class "Default")
      (node (ref "H1") (pin "1") (pinfunction "1_1") (pintype "passive"))
    )
    (net (code "114") (name "unconnected-(H2-Pad1)") (class "Default")
      (node (ref "H2") (pin "1") (pinfunction "1_1") (pintype "passive"))
    )
    (net (code "115") (name "unconnected-(H3-Pad1)") (class "Default")
      (node (ref "H3") (pin "1") (pinfunction "1_1") (pintype "passive"))
    )
    (net (code "116") (name "unconnected-(H4-Pad1)") (class "Default")
      (node (ref "H4") (pin "1") (pinfunction "1_1") (pintype "passive"))
    )
    (net (code "117") (name "unconnected-(J1-GND-PadS)") (class "Default")
      (node (ref "J1") (pin "S") (pinfunction "GND_S") (pintype "passive"))
    )
    (net (code "118") (name "unconnected-(J1-ID-Pad4)") (class "Default")
      (node (ref "J1") (pin "4") (pinfunction "ID_4") (pintype "passive+no_connect"))
    )
    (net (code "119") (name "unconnected-(J5-GND-PadS1)") (class "Default")
      (node (ref "J5") (pin "S1") (pinfunction "GND_S1") (pintype "passive"))
    )
    (net (code "120") (name "unconnected-(J5-GND-PadS2)") (class "Default")
      (node (ref "J5") (pin "S2") (pinfunction "GND_S2") (pintype "passive"))
    )
    (net (code "121") (name "unconnected-(J5-GND-PadS3)") (class "Default")
      (node (ref "J5") (pin "S3") (pinfunction "GND_S3") (pintype "passive"))
    )
    (net (code "122") (name "unconnected-(J5-GND-PadS4)") (class "Default")
      (node (ref "J5") (pin "S4") (pinfunction "GND_S4") (pintype "passive"))
    )
    (net (code "123") (name "unconnected-(J5-VPP-PadC6)") (class "Default")
      (node (ref "J5") (pin "C6") (pinfunction "VPP_C6") (pintype "passive+no_connect"))
    )
    (net (code "124") (name "unconnected-(M1-ADC-Pad38)") (class "Default")
      (node (ref "M1") (pin "38") (pinfunction "ADC_38") (pintype "passive+no_connect"))
    )
    (net (code "125") (name "unconnected-(M1-BT_ANT-Pad20)") (class "Default")
      (node (ref "M1") (pin "20") (pinfunction "BT_ANT_20") (pintype "passive+no_connect"))
    )
    (net (code "126") (name "unconnected-(M1-RF_SYNC-Pad29)") (class "Default")
      (node (ref "M1") (pin "29") (pinfunction "RF_SYNC_29") (pintype "passive+no_connect"))
    )
    (net (code "127") (name "unconnected-(M1-SIM_DET-Pad14)") (class "Default")
      (node (ref "M1") (pin "14") (pinfunction "SIM_DET_14") (pintype "passive+no_connect"))
    )
    (net (code "128") (name "unconnected-(M1-UART1_CTS-Pad4)") (class "Default")
      (node (ref "M1") (pin "4") (pinfunction "UART1_CTS_4") (pintype "passive+no_connect"))
    )
    (net (code "129") (name "unconnected-(M1-UART1_DCD-Pad5)") (class "Default")
      (node (ref "M1") (pin "5") (pinfunction "UART1_DCD_5") (pintype "passive+no_connect"))
    )
    (net (code "130") (name "unconnected-(M1-UART1_DTR-Pad6)") (class "Default")
      (node (ref "M1") (pin "6") (pinfunction "UART1_DTR_6") (pintype "passive+no_connect"))
    )
    (net (code "131") (name "unconnected-(M1-UART1_RI-Pad7)") (class "Default")
      (node (ref "M1") (pin "7") (pinfunction "UART1_RI_7") (pintype "passive+no_connect"))
    )
    (net (code "132") (name "unconnected-(M1-UART1_RTS-Pad3)") (class "Default")
      (node (ref "M1") (pin "3") (pinfunction "UART1_RTS_3") (pintype "passive+no_connect"))
    )
    (net (code "133") (name "unconnected-(M1-UART2_RXD-Pad23)") (class "Default")
      (node (ref "M1") (pin "23") (pinfunction "UART2_RXD_23") (pintype "passive+no_connect"))
    )
    (net (code "134") (name "unconnected-(M1-UART2_TXD-Pad22)") (class "Default")
      (node (ref "M1") (pin "22") (pinfunction "UART2_TXD_22") (pintype "passive+no_connect"))
    )
    (net (code "135") (name "unconnected-(M1-USB_DN-Pad26)") (class "Default")
      (node (ref "M1") (pin "26") (pinfunction "USB_DN_26") (pintype "passive+no_connect"))
    )
    (net (code "136") (name "unconnected-(M1-USB_DP-Pad25)") (class "Default")
      (node (ref "M1") (pin "25") (pinfunction "USB_DP_25") (pintype "passive+no_connect"))
    )
    (net (code "137") (name "unconnected-(M1-USB_VBUS-Pad24)") (class "Default")
      (node (ref "M1") (pin "24") (pinfunction "USB_VBUS_24") (pintype "passive+no_connect"))
    )
    (net (code "138") (name "unconnected-(M1-VDD_EXT-Pad40)") (class "Default")
      (node (ref "M1") (pin "40") (pinfunction "VDD_EXT_40") (pintype "passive+no_connect"))
    )
    (net (code "139") (name "unconnected-(SW1-NO1-Pad3)") (class "Default")
      (node (ref "SW1") (pin "3") (pinfunction "NO1_3") (pintype "passive"))
    )
    (net (code "140") (name "unconnected-(U1-TD-Pad4)") (class "Default")
      (node (ref "U1") (pin "4") (pinfunction "TD_4") (pintype "passive+no_connect"))
    )
    (net (code "141") (name "unconnected-(U2-CE-Pad8)") (class "Default")
      (node (ref "U2") (pin "8") (pinfunction "CE_8") (pintype "passive+no_connect"))
    )
    (net (code "142") (name "unconnected-(U3-D12-Pad1)") (class "Default")
      (node (ref "U3") (pin "1") (pinfunction "D12_1") (pintype "passive+no_connect"))
    )
    (net (code "143") (name "unconnected-(U3-D12-Pad8)") (class "Default")
      (node (ref "U3") (pin "8") (pinfunction "D12_8") (pintype "passive+no_connect"))
    )
    (net (code "144") (name "unconnected-(U4-A6{slash}ADC6-Pad19)") (class "Default")
      (node (ref "U4") (pin "19") (pinfunction "A6/ADC6_19") (pintype "passive+no_connect"))
    )
    (net (code "145") (name "unconnected-(U4-A7{slash}ADC7-Pad22)") (class "Default")
      (node (ref "U4") (pin "22") (pinfunction "A7/ADC7_22") (pintype "passive+no_connect"))
    )
    (net (code "146") (name "unconnected-(U5-NC-Pad6)") (class "Default")
      (node (ref "U5") (pin "6") (pinfunction "NC_6") (pintype "passive+no_connect"))
    )
    (net (code "147") (name "unconnected-(U6-CTS#-Pad9)") (class "Default")
      (node (ref "U6") (pin "9") (pinfunction "CTS#_9") (pintype "passive+no_connect"))
    )
    (net (code "148") (name "unconnected-(U6-DCD#-Pad12)") (class "Default")
      (node (ref "U6") (pin "12") (pinfunction "DCD#_12") (pintype "passive+no_connect"))
    )
    (net (code "149") (name "unconnected-(U6-DTR#-Pad13)") (class "Default")
      (node (ref "U6") (pin "13") (pinfunction "DTR#_13") (pintype "passive+no_connect"))
    )
    (net (code "150") (name "unconnected-(U6-NC-Pad7)") (class "Default")
      (node (ref "U6") (pin "7") (pinfunction "NC_7") (pintype "passive+no_connect"))
    )
    (net (code "151") (name "unconnected-(U6-NC-Pad8)") (class "Default")
      (node (ref "U6") (pin "8") (pinfunction "NC_8") (pintype "passive+no_connect"))
    )
    (net (code "152") (name "unconnected-(U6-R232-Pad15)") (class "Default")
      (node (ref "U6") (pin "15") (pinfunction "R232_15") (pintype "passive+no_connect"))
    )
    (net (code "153") (name "unconnected-(U6-RI#-Pad11)") (class "Default")
      (node (ref "U6") (pin "11") (pinfunction "RI#_11") (pintype "passive+no_connect"))
    )
    (net (code "154") (name "unconnected-(U6-RST#-Pad14)") (class "Default")
      (node (ref "U6") (pin "14") (pinfunction "RST#_14") (pintype "passive+no_connect"))
    )
  )
)
